# Sheet1.net
KiCad netlist of a schematic drawn in Altium Designer
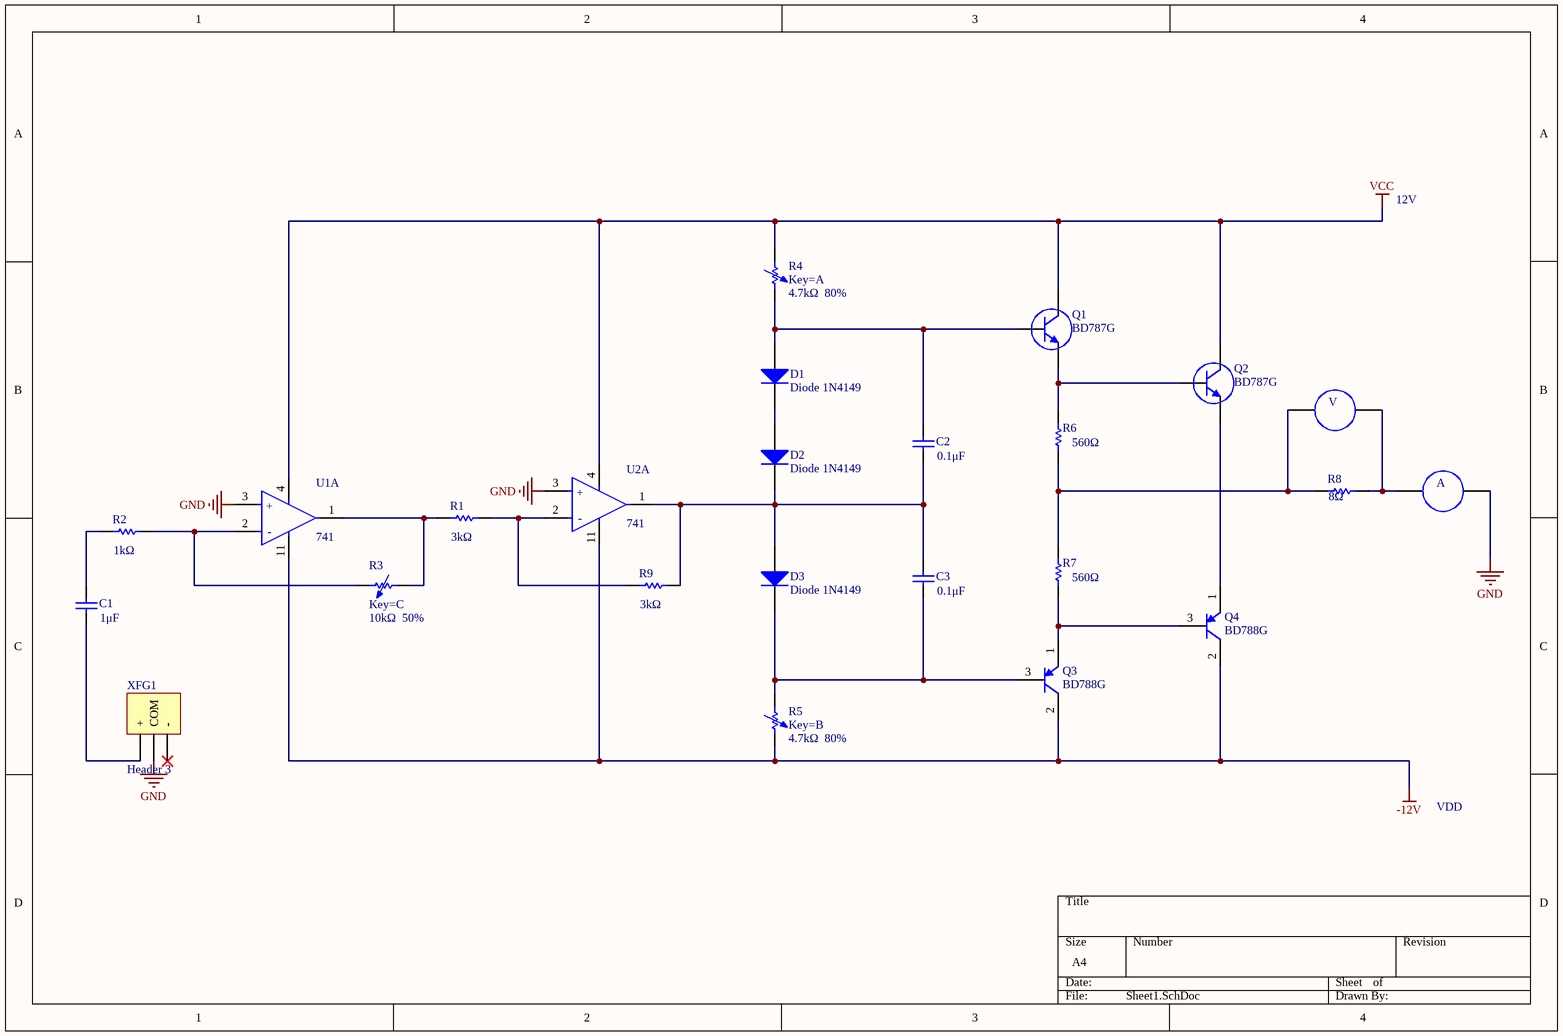
[diagram p0: Sheet1.SchDoc]

(export (version "E")
  (design (tool "Eeschema 10.0.6"))
  (components
    (comp (ref "A")
      (value "Meter")
      (footprint "RAD-0.1")
      (description "Indicating Instrument")
      (fields (field (name "PUBLISHER") "Altium Limited"))
      (libsource (lib "Miscellaneous Devices") (part "Meter"))
    )
    (comp (ref "C1")
      (value "1μF")
      (footprint "RAD-0.3")
      (description "Capacitor")
      (fields (field (name "PUBLISHER") "Altium Limited"))
      (libsource (lib "Miscellaneous Devices") (part "Cap"))
    )
    (comp (ref "C2")
      (value "0.1μF")
      (footprint "RAD-0.3")
      (description "Capacitor")
      (fields (field (name "Comment") "Cap") (field (name "PUBLISHER") "Altium Limited"))
      (libsource (lib "Miscellaneous Devices") (part "Cap"))
    )
    (comp (ref "C3")
      (value "0.1μF")
      (footprint "RAD-0.3")
      (description "Capacitor")
      (fields (field (name "Comment") "Cap") (field (name "PUBLISHER") "Altium Limited"))
      (libsource (lib "Miscellaneous Devices") (part "Cap"))
    )
    (comp (ref "D1")
      (value "Diode 1N4149")
      (footprint "DO-35A")
      (description "Computer Diode")
      (fields (field (name "PUBLISHER") "Altium Limited"))
      (libsource (lib "Miscellaneous Devices") (part "Diode 1N4149"))
    )
    (comp (ref "D2")
      (value "Diode 1N4149")
      (footprint "DO-35A")
      (description "Computer Diode")
      (fields (field (name "PUBLISHER") "Altium Limited"))
      (libsource (lib "Miscellaneous Devices") (part "Diode 1N4149"))
    )
    (comp (ref "D3")
      (value "Diode 1N4149")
      (footprint "DO-35A")
      (description "Computer Diode")
      (fields (field (name "PUBLISHER") "Altium Limited"))
      (libsource (lib "Miscellaneous Devices") (part "Diode 1N4149"))
    )
    (comp (ref "Q1")
      (value "BD787G")
      (footprint "ONSC-TO-225-3-77-09")
      (description "BD Series 60 V 4 A PNP Complementary Plastic Silicon Power Transistor TO-220 AB")
      (libsource (lib "嘉俊 何") (part "TRANS-NPN-3"))
    )
    (comp (ref "Q2")
      (value "BD787G")
      (footprint "ONSC-TO-225-3-77-09")
      (description "BD Series 60 V 4 A PNP Complementary Plastic Silicon Power Transistor TO-220 AB")
      (libsource (lib "嘉俊 何") (part "TRANS-NPN-3"))
    )
    (comp (ref "Q3")
      (value "BD788G")
      (footprint "ONSC-TO-225-3-77-09")
      (description "Complementary Plastic Silicon Power Transistor, 3-Pin TO-225, Pb-Free, Bulk Box")
      (fields (field (name "MANUFACTURER") "On Semiconductor"))
      (libsource (lib "Altium Content Vault") (part "ONSC-PNP-E1C2B3-3"))
    )
    (comp (ref "Q4")
      (value "BD788G")
      (footprint "ONSC-TO-225-3-77-09")
      (description "Complementary Plastic Silicon Power Transistor, 3-Pin TO-225, Pb-Free, Bulk Box")
      (fields (field (name "MANUFACTURER") "On Semiconductor"))
      (libsource (lib "Altium Content Vault") (part "ONSC-PNP-E1C2B3-3"))
    )
    (comp (ref "R1")
      (value "3kΩ")
      (footprint "AXIAL-0.3")
      (description "Resistor")
      (fields (field (name "Comment") "Res1") (field (name "PUBLISHER") "Altium Limited"))
      (libsource (lib "Miscellaneous Devices") (part "Res1"))
    )
    (comp (ref "R2")
      (value "1kΩ")
      (footprint "AXIAL-0.3")
      (description "Resistor")
      (fields (field (name "PUBLISHER") "Altium Limited"))
      (libsource (lib "Miscellaneous Devices") (part "Res1"))
    )
    (comp (ref "R3")
      (value "Key=C")
      (footprint "AXIAL-0.7")
      (description "Variable Resistor")
      (fields (field (name "ALTIUM_VALUE") "10kΩ  50%") (field (name "PUBLISHER") "Altium Limited"))
      (libsource (lib "Miscellaneous Devices") (part "Res Adj1"))
    )
    (comp (ref "R4")
      (value "Key=A")
      (footprint "AXIAL-0.7")
      (description "Variable Resistor")
      (fields (field (name "ALTIUM_VALUE") "4.7kΩ  80%") (field (name "PUBLISHER") "Altium Limited"))
      (libsource (lib "Miscellaneous Devices") (part "Res Adj1"))
    )
    (comp (ref "R5")
      (value "Key=B")
      (footprint "AXIAL-0.7")
      (description "Variable Resistor")
      (fields (field (name "ALTIUM_VALUE") "4.7kΩ  80%") (field (name "PUBLISHER") "Altium Limited"))
      (libsource (lib "Miscellaneous Devices") (part "Res Adj1"))
    )
    (comp (ref "R6")
      (value "560Ω")
      (footprint "AXIAL-0.3")
      (description "Resistor")
      (fields (field (name "Comment") "Res1") (field (name "PUBLISHER") "Altium Limited"))
      (libsource (lib "Miscellaneous Devices") (part "Res1"))
    )
    (comp (ref "R7")
      (value "560Ω")
      (footprint "AXIAL-0.3")
      (description "Resistor")
      (fields (field (name "Comment") "Res1") (field (name "PUBLISHER") "Altium Limited"))
      (libsource (lib "Miscellaneous Devices") (part "Res1"))
    )
    (comp (ref "R8")
      (value "8Ω")
      (footprint "AXIAL-0.3")
      (description "Resistor")
      (fields (field (name "Comment") "Res1") (field (name "PUBLISHER") "Altium Limited"))
      (libsource (lib "Miscellaneous Devices") (part "Res1"))
    )
    (comp (ref "R9")
      (value "3kΩ")
      (footprint "AXIAL-0.3")
      (description "Resistor")
      (fields (field (name "Comment") "Res1") (field (name "PUBLISHER") "Altium Limited"))
      (libsource (lib "Miscellaneous Devices") (part "Res1"))
    )
    (comp (ref "U1")
      (value "741")
      (footprint "FP-N-14-MFG")
      (description "IC OPAMP GP 4 CIRCUIT 14DIP")
      (libsource (lib "Altium Content Vault") (part "684fa0f315d4229452f837ea2b10642"))
    )
    (comp (ref "U2")
      (value "741")
      (footprint "FP-N-14-MFG")
      (description "IC OPAMP GP 4 CIRCUIT 14DIP")
      (libsource (lib "Altium Content Vault") (part "684fa0f315d4229452f837ea2b10642"))
    )
    (comp (ref "V")
      (value "Meter")
      (footprint "RAD-0.1")
      (description "Indicating Instrument")
      (fields (field (name "PUBLISHER") "Altium Limited"))
      (libsource (lib "Miscellaneous Devices") (part "Meter"))
    )
    (comp (ref "XFG1")
      (value "Header 3")
      (footprint "HDR1X3")
      (description "Header, 3-Pin")
      (fields (field (name "PUBLISHER") "Altium Limited"))
      (libsource (lib "Miscellaneous Connectors") (part "Header 3"))
    )
  )
  (nets
    (net (code "1") (name "-12V") (class "Default")
      (node (ref "Q3") (pin "2") (pinfunction "C_2") (pintype "passive"))
      (node (ref "Q4") (pin "2") (pinfunction "C_2") (pintype "passive"))
      (node (ref "R5") (pin "2") (pinfunction "2_2") (pintype "passive"))
      (node (ref "U1") (pin "11") (pinfunction "V-_11") (pintype "power_in"))
      (node (ref "U2") (pin "11") (pinfunction "V-_11") (pintype "power_in"))
    )
    (net (code "2") (name "GND") (class "Default")
      (node (ref "A") (pin "2") (pinfunction "2_2") (pintype "passive"))
      (node (ref "U1") (pin "3") (pinfunction "+IN_A_3") (pintype "tri_state"))
      (node (ref "U2") (pin "3") (pinfunction "+IN_A_3") (pintype "tri_state"))
      (node (ref "XFG1") (pin "2") (pinfunction "COM_2") (pintype "passive"))
    )
    (net (code "3") (name "Net-(A-Pad1)") (class "Default")
      (node (ref "A") (pin "1") (pinfunction "1_1") (pintype "passive"))
      (node (ref "R8") (pin "2") (pinfunction "2_2") (pintype "passive"))
      (node (ref "V") (pin "2") (pinfunction "2_2") (pintype "passive"))
    )
    (net (code "4") (name "Net-(C1-Pad2)") (class "Default")
      (node (ref "C1") (pin "2") (pinfunction "2_2") (pintype "passive"))
      (node (ref "R2") (pin "1") (pinfunction "1_1") (pintype "passive"))
    )
    (net (code "5") (name "Net-(D1-A)") (class "Default")
      (node (ref "C2") (pin "2") (pinfunction "2_2") (pintype "passive"))
      (node (ref "D1") (pin "1") (pinfunction "A_1") (pintype "passive"))
      (node (ref "Q1") (pin "2") (pinfunction "B_2") (pintype "passive"))
      (node (ref "R4") (pin "2") (pinfunction "2_2") (pintype "passive"))
    )
    (net (code "6") (name "Net-(D1-K)") (class "Default")
      (node (ref "D1") (pin "2") (pinfunction "K_2") (pintype "passive"))
      (node (ref "D2") (pin "1") (pinfunction "A_1") (pintype "passive"))
    )
    (net (code "7") (name "Net-(D2-K)") (class "Default")
      (node (ref "C2") (pin "1") (pinfunction "1_1") (pintype "passive"))
      (node (ref "C3") (pin "2") (pinfunction "2_2") (pintype "passive"))
      (node (ref "D2") (pin "2") (pinfunction "K_2") (pintype "passive"))
      (node (ref "D3") (pin "1") (pinfunction "A_1") (pintype "passive"))
      (node (ref "R9") (pin "2") (pinfunction "2_2") (pintype "passive"))
      (node (ref "U2") (pin "1") (pinfunction "OUT_A_1") (pintype "passive"))
    )
    (net (code "8") (name "Net-(D3-K)") (class "Default")
      (node (ref "C3") (pin "1") (pinfunction "1_1") (pintype "passive"))
      (node (ref "D3") (pin "2") (pinfunction "K_2") (pintype "passive"))
      (node (ref "Q3") (pin "3") (pinfunction "B_3") (pintype "passive"))
      (node (ref "R5") (pin "1") (pinfunction "1_1") (pintype "passive"))
    )
    (net (code "9") (name "Net-(Q1-E)") (class "Default")
      (node (ref "Q1") (pin "1") (pinfunction "E_1") (pintype "passive"))
      (node (ref "Q2") (pin "2") (pinfunction "B_2") (pintype "passive"))
      (node (ref "R6") (pin "2") (pinfunction "2_2") (pintype "passive"))
    )
    (net (code "10") (name "Net-(Q2-E)") (class "Default")
      (node (ref "Q2") (pin "1") (pinfunction "E_1") (pintype "passive"))
      (node (ref "Q4") (pin "1") (pinfunction "E_1") (pintype "passive"))
    )
    (net (code "11") (name "Net-(Q3-E)") (class "Default")
      (node (ref "Q3") (pin "1") (pinfunction "E_1") (pintype "passive"))
      (node (ref "Q4") (pin "3") (pinfunction "B_3") (pintype "passive"))
      (node (ref "R7") (pin "1") (pinfunction "1_1") (pintype "passive"))
    )
    (net (code "12") (name "Net-(R6-Pad1)") (class "Default")
      (node (ref "R6") (pin "1") (pinfunction "1_1") (pintype "passive"))
      (node (ref "R7") (pin "2") (pinfunction "2_2") (pintype "passive"))
      (node (ref "R8") (pin "1") (pinfunction "1_1") (pintype "passive"))
      (node (ref "V") (pin "1") (pinfunction "1_1") (pintype "passive"))
    )
    (net (code "13") (name "Net-(U1A--IN_A)") (class "Default")
      (node (ref "R2") (pin "2") (pinfunction "2_2") (pintype "passive"))
      (node (ref "R3") (pin "2") (pinfunction "2_2") (pintype "passive"))
      (node (ref "U1") (pin "2") (pinfunction "-IN_A_2") (pintype "tri_state"))
    )
    (net (code "14") (name "Net-(U1A-OUT_A)") (class "Default")
      (node (ref "R1") (pin "1") (pinfunction "1_1") (pintype "passive"))
      (node (ref "R3") (pin "1") (pinfunction "1_1") (pintype "passive"))
      (node (ref "U1") (pin "1") (pinfunction "OUT_A_1") (pintype "passive"))
    )
    (net (code "15") (name "Net-(U2A--IN_A)") (class "Default")
      (node (ref "R1") (pin "2") (pinfunction "2_2") (pintype "passive"))
      (node (ref "R9") (pin "1") (pinfunction "1_1") (pintype "passive"))
      (node (ref "U2") (pin "2") (pinfunction "-IN_A_2") (pintype "tri_state"))
    )
    (net (code "16") (name "Net-(XFG1-+)") (class "Default")
      (node (ref "C1") (pin "1") (pinfunction "1_1") (pintype "passive"))
      (node (ref "XFG1") (pin "1") (pinfunction "+_1") (pintype "passive"))
    )
    (net (code "17") (name "VCC") (class "Default")
      (node (ref "Q1") (pin "3") (pinfunction "C_3") (pintype "passive"))
      (node (ref "Q2") (pin "3") (pinfunction "C_3") (pintype "passive"))
      (node (ref "R4") (pin "1") (pinfunction "1_1") (pintype "passive"))
      (node (ref "U1") (pin "4") (pinfunction "V+_4") (pintype "power_in"))
      (node (ref "U2") (pin "4") (pinfunction "V+_4") (pintype "power_in"))
    )
    (net (code "18") (name "unconnected-(XFG1---Pad3)") (class "Default")
      (node (ref "XFG1") (pin "3") (pinfunction "-_3") (pintype "passive+no_connect"))
    )
  )
)
